# Schematic.net
KiCad netlist of a schematic drawn in Altium Designer
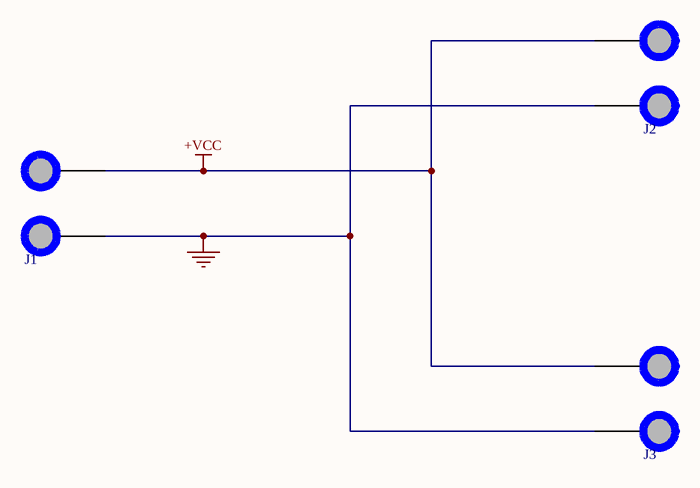
[diagram p0: Schematic.SchDoc]

(export (version "E")
  (design (tool "Eeschema 10.0.6"))
  (components
    (comp (ref "J1")
      (value "Doublepad")
      (footprint "DOUBLEPAD_WITH_HOLE_4MMx1MM5")
      (libsource (lib "SchLib") (part "DOUBLEPAD_WITH_HOLE_4MMx1MM5"))
    )
    (comp (ref "J2")
      (value "Doublepad")
      (footprint "DOUBLEPAD_WITH_HOLE_4MMx1MM5")
      (libsource (lib "SchLib") (part "DOUBLEPAD_WITH_HOLE_4MMx1MM5"))
    )
    (comp (ref "J3")
      (value "Doublepad")
      (footprint "DOUBLEPAD_WITH_HOLE_4MMx1MM5")
      (libsource (lib "SchLib") (part "DOUBLEPAD_WITH_HOLE_4MMx1MM5"))
    )
  )
  (nets
    (net (code "1") (name "+VCC") (class "Default")
      (node (ref "J1") (pin "1") (pinfunction "1_1") (pintype "passive"))
      (node (ref "J2") (pin "1") (pinfunction "1_1") (pintype "passive"))
      (node (ref "J3") (pin "1") (pinfunction "1_1") (pintype "passive"))
    )
    (net (code "2") (name "GND") (class "Default")
      (node (ref "J1") (pin "2") (pinfunction "2_2") (pintype "passive"))
      (node (ref "J2") (pin "2") (pinfunction "2_2") (pintype "passive"))
      (node (ref "J3") (pin "2") (pinfunction "2_2") (pintype "passive"))
    )
  )
)
